# dshield.net
KiCad netlist of a schematic drawn in EAGLE
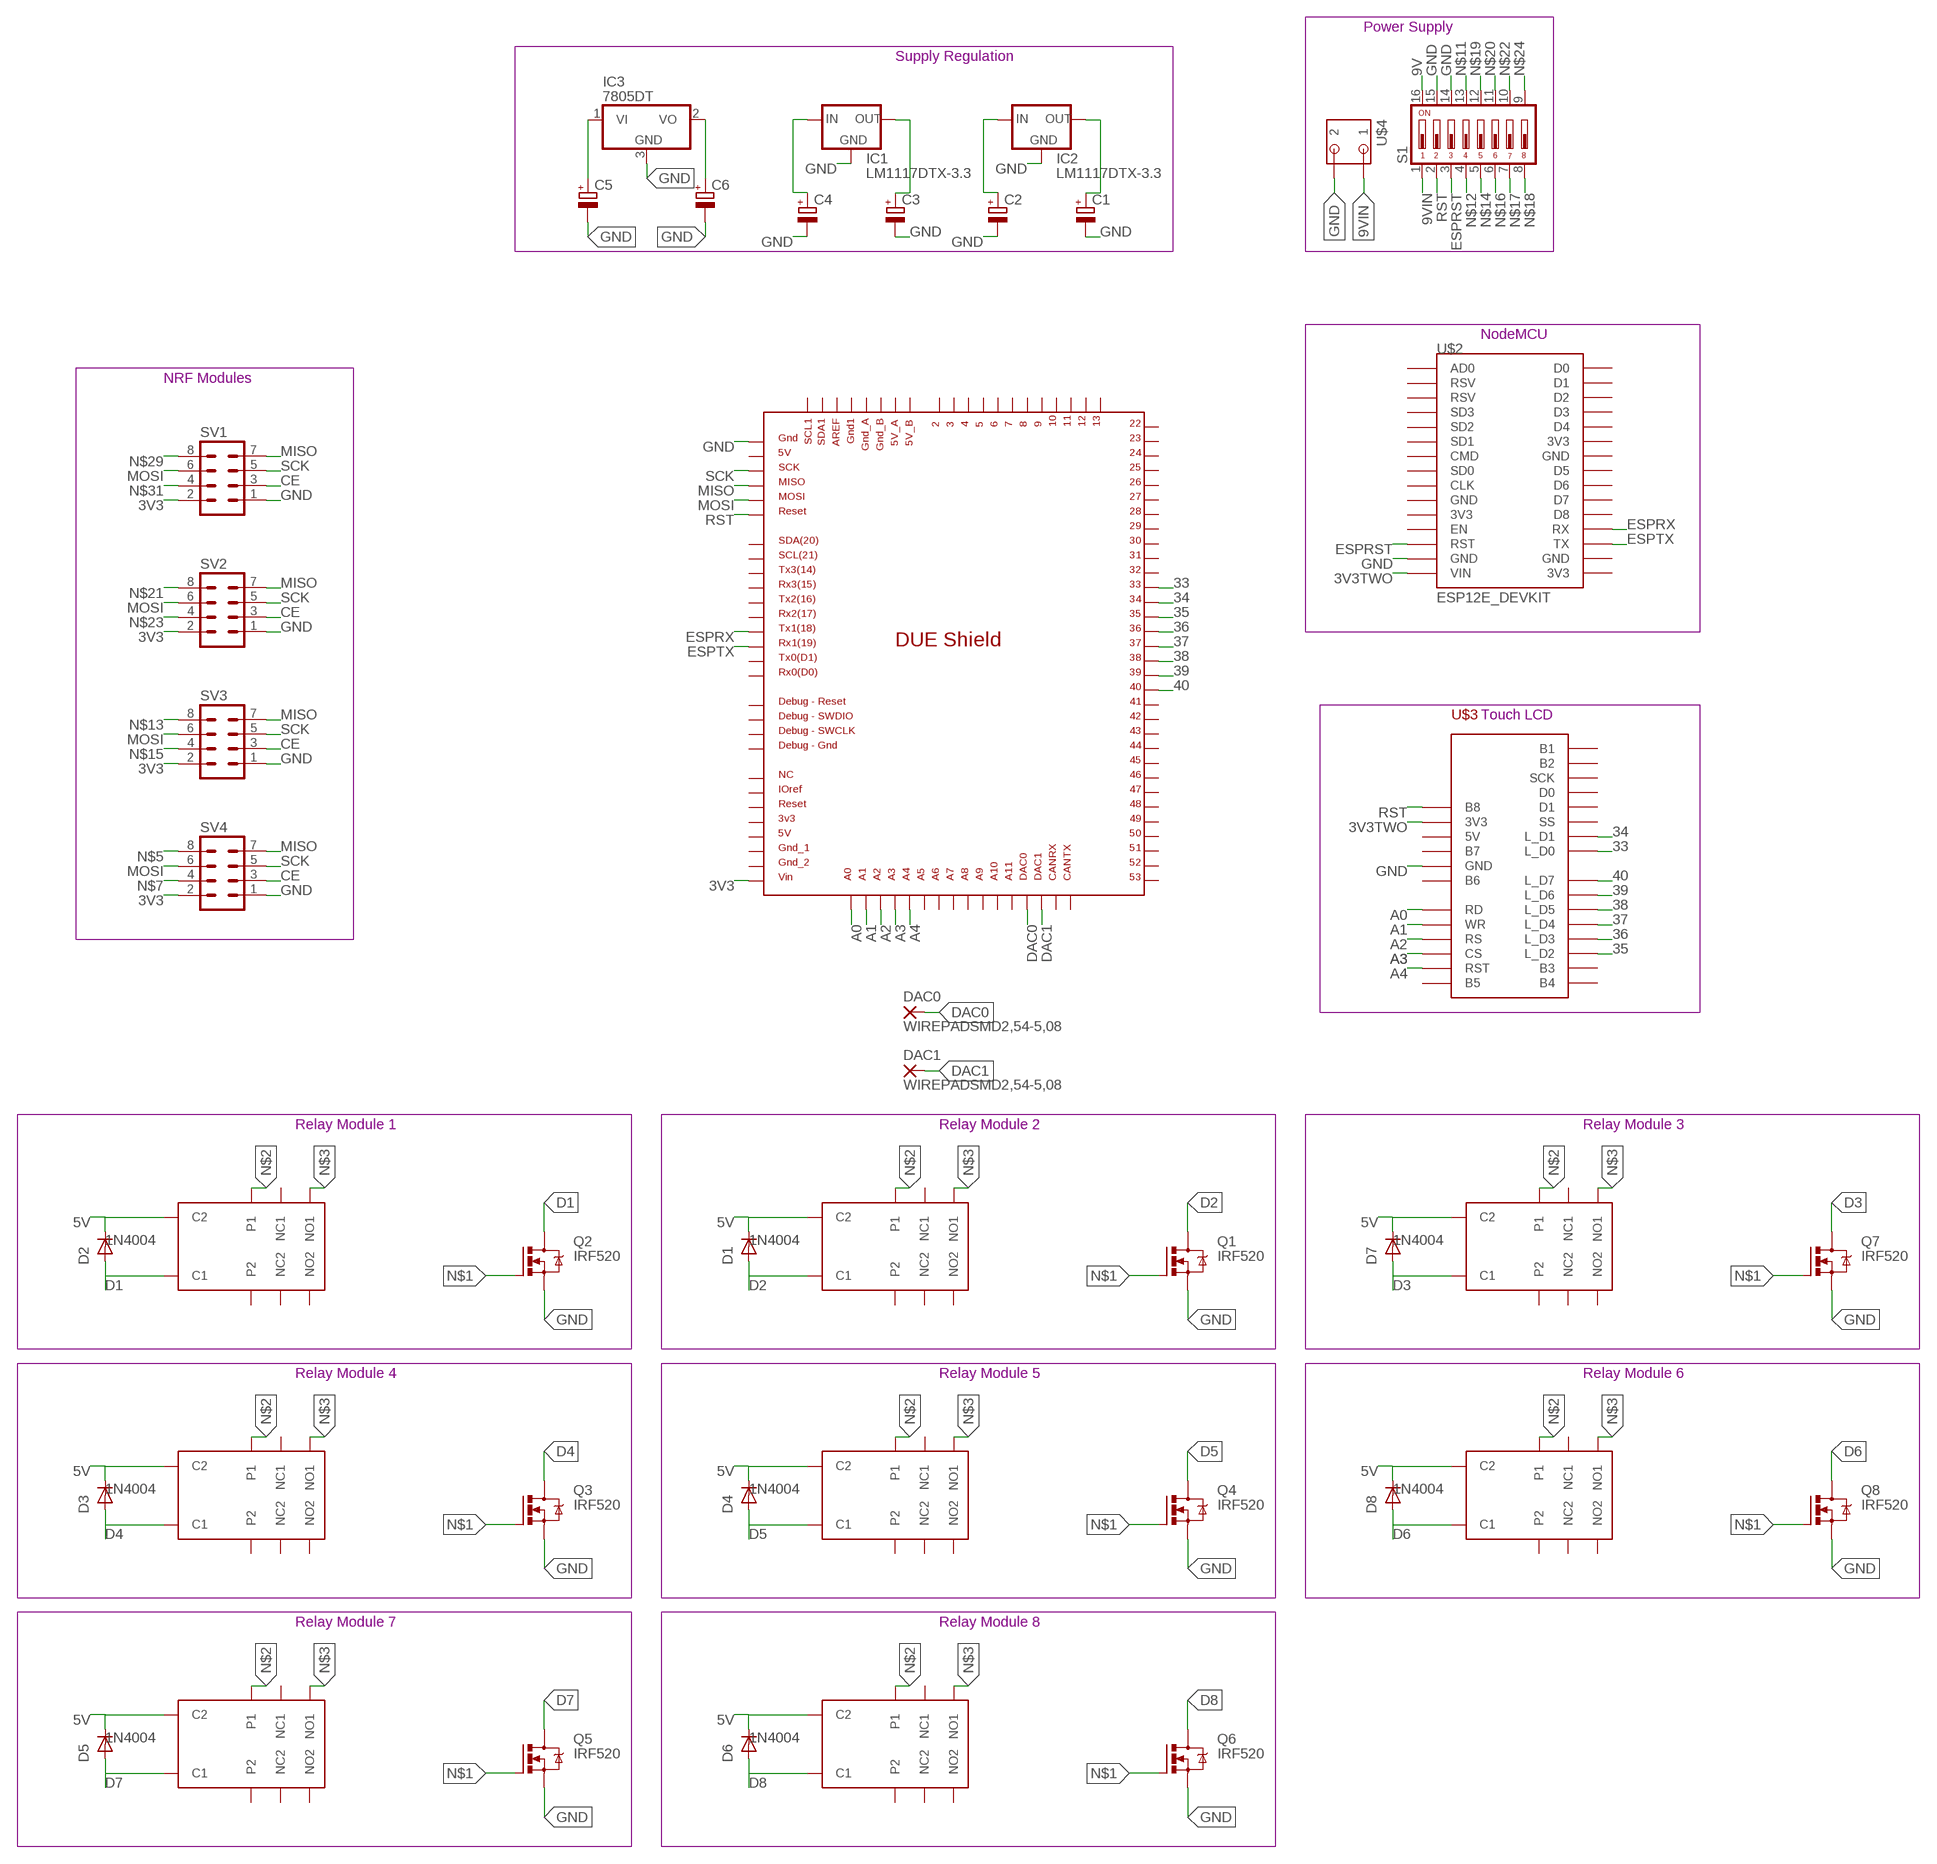
[diagram p0: schematic, sheet 1]

(export (version "E")
  (design (tool "Eeschema 10.0.6"))
  (components
    (comp (ref "BTPL1")
      (value "GS-SH-2XXT")
      (footprint "eagle-import:G_RELAY_SMD")
      (libsource (lib "eagle-import") (part "GS-SH-2XXT"))
    )
    (comp (ref "BTPL2")
      (value "GS-SH-2XXT")
      (footprint "eagle-import:G_RELAY_SMD")
      (libsource (lib "eagle-import") (part "GS-SH-2XXT"))
    )
    (comp (ref "BTPL3")
      (value "GS-SH-2XXT")
      (footprint "eagle-import:G_RELAY_SMD")
      (libsource (lib "eagle-import") (part "GS-SH-2XXT"))
    )
    (comp (ref "BTPL4")
      (value "GS-SH-2XXT")
      (footprint "eagle-import:G_RELAY_SMD")
      (libsource (lib "eagle-import") (part "GS-SH-2XXT"))
    )
    (comp (ref "BTPL5")
      (value "GS-SH-2XXT")
      (footprint "eagle-import:G_RELAY_SMD")
      (libsource (lib "eagle-import") (part "GS-SH-2XXT"))
    )
    (comp (ref "BTPL6")
      (value "GS-SH-2XXT")
      (footprint "eagle-import:G_RELAY_SMD")
      (libsource (lib "eagle-import") (part "GS-SH-2XXT"))
    )
    (comp (ref "BTPL7")
      (value "GS-SH-2XXT")
      (footprint "eagle-import:G_RELAY_SMD")
      (libsource (lib "eagle-import") (part "GS-SH-2XXT"))
    )
    (comp (ref "BTPL8")
      (value "GS-SH-2XXT")
      (footprint "eagle-import:G_RELAY_SMD")
      (libsource (lib "eagle-import") (part "GS-SH-2XXT"))
    )
    (comp (ref "C1")
      (value "CPOL-EUE2.5-6")
      (footprint "eagle-import:E2,5-6")
      (libsource (lib "eagle-import") (part "CPOL-EUE2.5-6"))
    )
    (comp (ref "C2")
      (value "CPOL-EUE2.5-6")
      (footprint "eagle-import:E2,5-6")
      (libsource (lib "eagle-import") (part "CPOL-EUE2.5-6"))
    )
    (comp (ref "C3")
      (value "CPOL-EUE2.5-6")
      (footprint "eagle-import:E2,5-6")
      (libsource (lib "eagle-import") (part "CPOL-EUE2.5-6"))
    )
    (comp (ref "C4")
      (value "CPOL-EUE2.5-6")
      (footprint "eagle-import:E2,5-6")
      (libsource (lib "eagle-import") (part "CPOL-EUE2.5-6"))
    )
    (comp (ref "C5")
      (value "CPOL-EUE2.5-6")
      (footprint "eagle-import:E2,5-6")
      (libsource (lib "eagle-import") (part "CPOL-EUE2.5-6"))
    )
    (comp (ref "C6")
      (value "CPOL-EUE2.5-6")
      (footprint "eagle-import:E2,5-6")
      (libsource (lib "eagle-import") (part "CPOL-EUE2.5-6"))
    )
    (comp (ref "D1")
      (value "1N4004")
      (footprint "eagle-import:DO41-10")
      (libsource (lib "eagle-import") (part "1N4004"))
    )
    (comp (ref "D2")
      (value "1N4004")
      (footprint "eagle-import:DO41-10")
      (libsource (lib "eagle-import") (part "1N4004"))
    )
    (comp (ref "D3")
      (value "1N4004")
      (footprint "eagle-import:DO41-10")
      (libsource (lib "eagle-import") (part "1N4004"))
    )
    (comp (ref "D4")
      (value "1N4004")
      (footprint "eagle-import:DO41-10")
      (libsource (lib "eagle-import") (part "1N4004"))
    )
    (comp (ref "D5")
      (value "1N4004")
      (footprint "eagle-import:DO41-10")
      (libsource (lib "eagle-import") (part "1N4004"))
    )
    (comp (ref "D6")
      (value "1N4004")
      (footprint "eagle-import:DO41-10")
      (libsource (lib "eagle-import") (part "1N4004"))
    )
    (comp (ref "D7")
      (value "1N4004")
      (footprint "eagle-import:DO41-10")
      (libsource (lib "eagle-import") (part "1N4004"))
    )
    (comp (ref "D8")
      (value "1N4004")
      (footprint "eagle-import:DO41-10")
      (libsource (lib "eagle-import") (part "1N4004"))
    )
    (comp (ref "DAC0")
      (value "WIREPADSMD2,54-5,08")
      (footprint "eagle-import:SMD2,54-5,08")
      (libsource (lib "eagle-import") (part "WIREPADSMD2,54-5,08"))
    )
    (comp (ref "DAC1")
      (value "WIREPADSMD2,54-5,08")
      (footprint "eagle-import:SMD2,54-5,08")
      (libsource (lib "eagle-import") (part "WIREPADSMD2,54-5,08"))
    )
    (comp (ref "IC1")
      (value "LM1117DTX-3.3")
      (footprint "eagle-import:TO252")
      (libsource (lib "eagle-import") (part "LM1117DTX-3.3"))
    )
    (comp (ref "IC2")
      (value "LM1117DTX-3.3")
      (footprint "eagle-import:TO252")
      (libsource (lib "eagle-import") (part "LM1117DTX-3.3"))
    )
    (comp (ref "IC3")
      (value "7805DT")
      (footprint "eagle-import:TO252")
      (libsource (lib "eagle-import") (part "78DT05"))
    )
    (comp (ref "Q1")
      (value "IRF520")
      (footprint "eagle-import:TO220BV")
      (libsource (lib "eagle-import") (part "IRF520"))
    )
    (comp (ref "Q2")
      (value "IRF520")
      (footprint "eagle-import:TO220BV")
      (libsource (lib "eagle-import") (part "IRF520"))
    )
    (comp (ref "Q3")
      (value "IRF520")
      (footprint "eagle-import:TO220BV")
      (libsource (lib "eagle-import") (part "IRF520"))
    )
    (comp (ref "Q4")
      (value "IRF520")
      (footprint "eagle-import:TO220BV")
      (libsource (lib "eagle-import") (part "IRF520"))
    )
    (comp (ref "Q5")
      (value "IRF520")
      (footprint "eagle-import:TO220BV")
      (libsource (lib "eagle-import") (part "IRF520"))
    )
    (comp (ref "Q6")
      (value "IRF520")
      (footprint "eagle-import:TO220BV")
      (libsource (lib "eagle-import") (part "IRF520"))
    )
    (comp (ref "Q7")
      (value "IRF520")
      (footprint "eagle-import:TO220BV")
      (libsource (lib "eagle-import") (part "IRF520"))
    )
    (comp (ref "Q8")
      (value "IRF520")
      (footprint "eagle-import:TO220BV")
      (libsource (lib "eagle-import") (part "IRF520"))
    )
    (comp (ref "S1")
      (value "DS08")
      (footprint "eagle-import:DS-08")
      (libsource (lib "eagle-import") (part "DS08"))
    )
    (comp (ref "SV1")
      (value "MA04-2")
      (footprint "eagle-import:MA04-2")
      (libsource (lib "eagle-import") (part "MA04-2"))
    )
    (comp (ref "SV2")
      (value "MA04-2")
      (footprint "eagle-import:MA04-2")
      (libsource (lib "eagle-import") (part "MA04-2"))
    )
    (comp (ref "SV3")
      (value "MA04-2")
      (footprint "eagle-import:MA04-2")
      (libsource (lib "eagle-import") (part "MA04-2"))
    )
    (comp (ref "SV4")
      (value "MA04-2")
      (footprint "eagle-import:MA04-2")
      (libsource (lib "eagle-import") (part "MA04-2"))
    )
    (comp (ref "U$1")
      (value "DUE(NORMAL)")
      (footprint "eagle-import:DUE(NORMAL)")
      (libsource (lib "eagle-import") (part "DUE(NORMAL)"))
    )
    (comp (ref "U$2")
      (value "ESP12E_DEVKIT")
      (footprint "eagle-import:ESP12E_DEVKIT")
      (libsource (lib "eagle-import") (part "ESP12E_DEVKIT"))
    )
    (comp (ref "U$3")
      (value "SPFD5408")
      (footprint "eagle-import:SPFD5408")
      (libsource (lib "eagle-import") (part "SPFD5408"))
    )
    (comp (ref "U$4")
      (value "SPTBB2-A2")
      (footprint "eagle-import:SPTB")
      (libsource (lib "eagle-import") (part "SPTBB2-A2"))
    )
  )
  (nets
    (net (code "1") (name "/3V3") (class "Default")
      (node (ref "C3") (pin "+") (pinfunction "+_+") (pintype "passive"))
      (node (ref "IC1") (pin "TAB") (pinfunction "OUT_TAB") (pintype "passive"))
      (node (ref "SV1") (pin "2") (pinfunction "2_2") (pintype "passive"))
      (node (ref "SV2") (pin "2") (pinfunction "2_2") (pintype "passive"))
      (node (ref "SV3") (pin "2") (pinfunction "2_2") (pintype "passive"))
      (node (ref "SV4") (pin "2") (pinfunction "2_2") (pintype "passive"))
      (node (ref "U$1") (pin "VIN") (pinfunction "VIN_VIN") (pintype "bidirectional"))
    )
    (net (code "2") (name "/3V3TWO") (class "Default")
      (node (ref "C1") (pin "+") (pinfunction "+_+") (pintype "passive"))
      (node (ref "IC2") (pin "TAB") (pinfunction "OUT_TAB") (pintype "passive"))
      (node (ref "U$2") (pin "VIN") (pinfunction "VIN_VIN") (pintype "bidirectional"))
      (node (ref "U$3") (pin "3V3") (pinfunction "3V3_3V3") (pintype "bidirectional"))
    )
    (net (code "3") (name "/5V") (class "Default")
      (node (ref "BTPL1") (pin "C2") (pinfunction "C2_C2") (pintype "bidirectional"))
      (node (ref "BTPL2") (pin "C2") (pinfunction "C2_C2") (pintype "bidirectional"))
      (node (ref "BTPL3") (pin "C2") (pinfunction "C2_C2") (pintype "bidirectional"))
      (node (ref "BTPL4") (pin "C2") (pinfunction "C2_C2") (pintype "bidirectional"))
      (node (ref "BTPL5") (pin "C2") (pinfunction "C2_C2") (pintype "bidirectional"))
      (node (ref "BTPL6") (pin "C2") (pinfunction "C2_C2") (pintype "bidirectional"))
      (node (ref "BTPL7") (pin "C2") (pinfunction "C2_C2") (pintype "bidirectional"))
      (node (ref "BTPL8") (pin "C2") (pinfunction "C2_C2") (pintype "bidirectional"))
      (node (ref "C6") (pin "+") (pinfunction "+_+") (pintype "passive"))
      (node (ref "D1") (pin "C") (pinfunction "C_C") (pintype "passive"))
      (node (ref "D2") (pin "C") (pinfunction "C_C") (pintype "passive"))
      (node (ref "D3") (pin "C") (pinfunction "C_C") (pintype "passive"))
      (node (ref "D4") (pin "C") (pinfunction "C_C") (pintype "passive"))
      (node (ref "D5") (pin "C") (pinfunction "C_C") (pintype "passive"))
      (node (ref "D6") (pin "C") (pinfunction "C_C") (pintype "passive"))
      (node (ref "D7") (pin "C") (pinfunction "C_C") (pintype "passive"))
      (node (ref "D8") (pin "C") (pinfunction "C_C") (pintype "passive"))
      (node (ref "IC3") (pin "2") (pinfunction "VO_2") (pintype "passive"))
    )
    (net (code "4") (name "/9V") (class "Default")
      (node (ref "C2") (pin "+") (pinfunction "+_+") (pintype "passive"))
      (node (ref "C4") (pin "+") (pinfunction "+_+") (pintype "passive"))
      (node (ref "C5") (pin "+") (pinfunction "+_+") (pintype "passive"))
      (node (ref "IC1") (pin "2") (pinfunction "IN_2") (pintype "input"))
      (node (ref "IC2") (pin "2") (pinfunction "IN_2") (pintype "input"))
      (node (ref "IC3") (pin "1") (pinfunction "VI_1") (pintype "input"))
      (node (ref "S1") (pin "16") (pinfunction "16_16") (pintype "passive"))
    )
    (net (code "5") (name "/33") (class "Default")
      (node (ref "U$1") (pin "33") (pinfunction "33_33") (pintype "bidirectional"))
      (node (ref "U$3") (pin "L_D0") (pinfunction "L_D0_L_D0") (pintype "bidirectional"))
    )
    (net (code "6") (name "/34") (class "Default")
      (node (ref "U$1") (pin "34") (pinfunction "34_34") (pintype "bidirectional"))
      (node (ref "U$3") (pin "L_D1") (pinfunction "L_D1_L_D1") (pintype "bidirectional"))
    )
    (net (code "7") (name "/35") (class "Default")
      (node (ref "U$1") (pin "35") (pinfunction "35_35") (pintype "bidirectional"))
      (node (ref "U$3") (pin "L_D2") (pinfunction "L_D2_L_D2") (pintype "bidirectional"))
    )
    (net (code "8") (name "/36") (class "Default")
      (node (ref "U$1") (pin "36") (pinfunction "36_36") (pintype "bidirectional"))
      (node (ref "U$3") (pin "L_D3") (pinfunction "L_D3_L_D3") (pintype "bidirectional"))
    )
    (net (code "9") (name "/37") (class "Default")
      (node (ref "U$1") (pin "37") (pinfunction "37_37") (pintype "bidirectional"))
      (node (ref "U$3") (pin "L_D4") (pinfunction "L_D4_L_D4") (pintype "bidirectional"))
    )
    (net (code "10") (name "/38") (class "Default")
      (node (ref "U$1") (pin "38") (pinfunction "38_38") (pintype "bidirectional"))
      (node (ref "U$3") (pin "L_D5") (pinfunction "L_D5_L_D5") (pintype "bidirectional"))
    )
    (net (code "11") (name "/39") (class "Default")
      (node (ref "U$1") (pin "39") (pinfunction "39_39") (pintype "bidirectional"))
      (node (ref "U$3") (pin "L_D6") (pinfunction "L_D6_L_D6") (pintype "bidirectional"))
    )
    (net (code "12") (name "/40") (class "Default")
      (node (ref "U$1") (pin "40") (pinfunction "40_40") (pintype "bidirectional"))
      (node (ref "U$3") (pin "L_D7") (pinfunction "L_D7_L_D7") (pintype "bidirectional"))
    )
    (net (code "13") (name "/A0") (class "Default")
      (node (ref "U$1") (pin "A0") (pinfunction "A0_A0") (pintype "bidirectional"))
      (node (ref "U$3") (pin "RD") (pinfunction "RD_RD") (pintype "bidirectional"))
    )
    (net (code "14") (name "/A1") (class "Default")
      (node (ref "U$1") (pin "A1") (pinfunction "A1_A1") (pintype "bidirectional"))
      (node (ref "U$3") (pin "WR") (pinfunction "WR_WR") (pintype "bidirectional"))
    )
    (net (code "15") (name "/A2") (class "Default")
      (node (ref "U$1") (pin "A2") (pinfunction "A2_A2") (pintype "bidirectional"))
      (node (ref "U$3") (pin "RS") (pinfunction "RS_RS") (pintype "bidirectional"))
    )
    (net (code "16") (name "/A3") (class "Default")
      (node (ref "U$1") (pin "A3") (pinfunction "A3_A3") (pintype "bidirectional"))
      (node (ref "U$3") (pin "CS") (pinfunction "CS_CS") (pintype "bidirectional"))
    )
    (net (code "17") (name "/A4") (class "Default")
      (node (ref "U$1") (pin "A4") (pinfunction "A4_A4") (pintype "bidirectional"))
      (node (ref "U$3") (pin "RST") (pinfunction "RST_RST") (pintype "bidirectional"))
    )
    (net (code "18") (name "/CE") (class "Default")
      (node (ref "SV1") (pin "3") (pinfunction "3_3") (pintype "passive"))
      (node (ref "SV2") (pin "3") (pinfunction "3_3") (pintype "passive"))
      (node (ref "SV3") (pin "3") (pinfunction "3_3") (pintype "passive"))
      (node (ref "SV4") (pin "3") (pinfunction "3_3") (pintype "passive"))
    )
    (net (code "19") (name "/ESPRST") (class "Default")
      (node (ref "S1") (pin "3") (pinfunction "3_3") (pintype "passive"))
      (node (ref "U$2") (pin "RST") (pinfunction "RST_RST") (pintype "bidirectional"))
    )
    (net (code "20") (name "/ESPRX") (class "Default")
      (node (ref "U$1") (pin "TX1") (pinfunction "TX1_TX1") (pintype "bidirectional"))
      (node (ref "U$2") (pin "RX") (pinfunction "RX_RX") (pintype "bidirectional"))
    )
    (net (code "21") (name "/ESPTX") (class "Default")
      (node (ref "U$1") (pin "RX1") (pinfunction "RX1_RX1") (pintype "bidirectional"))
      (node (ref "U$2") (pin "TX") (pinfunction "TX_TX") (pintype "bidirectional"))
    )
    (net (code "22") (name "/MISO") (class "Default")
      (node (ref "SV1") (pin "7") (pinfunction "7_7") (pintype "passive"))
      (node (ref "SV2") (pin "7") (pinfunction "7_7") (pintype "passive"))
      (node (ref "SV3") (pin "7") (pinfunction "7_7") (pintype "passive"))
      (node (ref "SV4") (pin "7") (pinfunction "7_7") (pintype "passive"))
      (node (ref "U$1") (pin "MISO_ICSP") (pinfunction "MISO_ICSP_MISO_ICSP") (pintype "bidirectional"))
    )
    (net (code "23") (name "/MOSI") (class "Default")
      (node (ref "SV1") (pin "6") (pinfunction "6_6") (pintype "passive"))
      (node (ref "SV2") (pin "6") (pinfunction "6_6") (pintype "passive"))
      (node (ref "SV3") (pin "6") (pinfunction "6_6") (pintype "passive"))
      (node (ref "SV4") (pin "6") (pinfunction "6_6") (pintype "passive"))
      (node (ref "U$1") (pin "MOSI_ICSP") (pinfunction "MOSI_ICSP_MOSI_ICSP") (pintype "bidirectional"))
    )
    (net (code "24") (name "/N$5") (class "Default")
      (node (ref "SV4") (pin "8") (pinfunction "8_8") (pintype "passive"))
    )
    (net (code "25") (name "/N$7") (class "Default")
      (node (ref "SV4") (pin "4") (pinfunction "4_4") (pintype "passive"))
    )
    (net (code "26") (name "/N$11") (class "Default")
      (node (ref "S1") (pin "13") (pinfunction "13_13") (pintype "passive"))
    )
    (net (code "27") (name "/N$12") (class "Default")
      (node (ref "S1") (pin "4") (pinfunction "4_4") (pintype "passive"))
    )
    (net (code "28") (name "/N$13") (class "Default")
      (node (ref "SV3") (pin "8") (pinfunction "8_8") (pintype "passive"))
    )
    (net (code "29") (name "/N$14") (class "Default")
      (node (ref "S1") (pin "5") (pinfunction "5_5") (pintype "passive"))
    )
    (net (code "30") (name "/N$15") (class "Default")
      (node (ref "SV3") (pin "4") (pinfunction "4_4") (pintype "passive"))
    )
    (net (code "31") (name "/N$16") (class "Default")
      (node (ref "S1") (pin "6") (pinfunction "6_6") (pintype "passive"))
    )
    (net (code "32") (name "/N$17") (class "Default")
      (node (ref "S1") (pin "7") (pinfunction "7_7") (pintype "passive"))
    )
    (net (code "33") (name "/N$18") (class "Default")
      (node (ref "S1") (pin "8") (pinfunction "8_8") (pintype "passive"))
    )
    (net (code "34") (name "/N$19") (class "Default")
      (node (ref "S1") (pin "12") (pinfunction "12_12") (pintype "passive"))
    )
    (net (code "35") (name "/N$20") (class "Default")
      (node (ref "S1") (pin "11") (pinfunction "11_11") (pintype "passive"))
    )
    (net (code "36") (name "/N$21") (class "Default")
      (node (ref "SV2") (pin "8") (pinfunction "8_8") (pintype "passive"))
    )
    (net (code "37") (name "/N$22") (class "Default")
      (node (ref "S1") (pin "10") (pinfunction "10_10") (pintype "passive"))
    )
    (net (code "38") (name "/N$23") (class "Default")
      (node (ref "SV2") (pin "4") (pinfunction "4_4") (pintype "passive"))
    )
    (net (code "39") (name "/N$24") (class "Default")
      (node (ref "S1") (pin "9") (pinfunction "9_9") (pintype "passive"))
    )
    (net (code "40") (name "/N$29") (class "Default")
      (node (ref "SV1") (pin "8") (pinfunction "8_8") (pintype "passive"))
    )
    (net (code "41") (name "/N$31") (class "Default")
      (node (ref "SV1") (pin "4") (pinfunction "4_4") (pintype "passive"))
    )
    (net (code "42") (name "/RST") (class "Default")
      (node (ref "S1") (pin "2") (pinfunction "2_2") (pintype "passive"))
      (node (ref "U$1") (pin "RESET_ICSP") (pinfunction "RESET_ICSP_RESET_ICSP") (pintype "bidirectional"))
      (node (ref "U$3") (pin "B8") (pinfunction "B8_B8") (pintype "bidirectional"))
    )
    (net (code "43") (name "/SCK") (class "Default")
      (node (ref "SV1") (pin "5") (pinfunction "5_5") (pintype "passive"))
      (node (ref "SV2") (pin "5") (pinfunction "5_5") (pintype "passive"))
      (node (ref "SV3") (pin "5") (pinfunction "5_5") (pintype "passive"))
      (node (ref "SV4") (pin "5") (pinfunction "5_5") (pintype "passive"))
      (node (ref "U$1") (pin "SCK_ICSP") (pinfunction "SCK_ICSP_SCK_ICSP") (pintype "bidirectional"))
    )
    (net (code "44") (name "9VIN") (class "Default")
      (node (ref "S1") (pin "1") (pinfunction "1_1") (pintype "passive"))
      (node (ref "U$4") (pin "B2") (pinfunction "1_B2") (pintype "bidirectional"))
    )
    (net (code "45") (name "D1") (class "Default")
      (node (ref "BTPL2") (pin "C1") (pinfunction "C1_C1") (pintype "bidirectional"))
      (node (ref "D2") (pin "A") (pinfunction "A_A") (pintype "passive"))
      (node (ref "Q2") (pin "D") (pinfunction "D_D") (pintype "passive"))
    )
    (net (code "46") (name "D2") (class "Default")
      (node (ref "BTPL1") (pin "C1") (pinfunction "C1_C1") (pintype "bidirectional"))
      (node (ref "D1") (pin "A") (pinfunction "A_A") (pintype "passive"))
      (node (ref "Q1") (pin "D") (pinfunction "D_D") (pintype "passive"))
    )
    (net (code "47") (name "D3") (class "Default")
      (node (ref "BTPL7") (pin "C1") (pinfunction "C1_C1") (pintype "bidirectional"))
      (node (ref "D7") (pin "A") (pinfunction "A_A") (pintype "passive"))
      (node (ref "Q7") (pin "D") (pinfunction "D_D") (pintype "passive"))
    )
    (net (code "48") (name "D4") (class "Default")
      (node (ref "BTPL3") (pin "C1") (pinfunction "C1_C1") (pintype "bidirectional"))
      (node (ref "D3") (pin "A") (pinfunction "A_A") (pintype "passive"))
      (node (ref "Q3") (pin "D") (pinfunction "D_D") (pintype "passive"))
    )
    (net (code "49") (name "D5") (class "Default")
      (node (ref "BTPL4") (pin "C1") (pinfunction "C1_C1") (pintype "bidirectional"))
      (node (ref "D4") (pin "A") (pinfunction "A_A") (pintype "passive"))
      (node (ref "Q4") (pin "D") (pinfunction "D_D") (pintype "passive"))
    )
    (net (code "50") (name "D6") (class "Default")
      (node (ref "BTPL8") (pin "C1") (pinfunction "C1_C1") (pintype "bidirectional"))
      (node (ref "D8") (pin "A") (pinfunction "A_A") (pintype "passive"))
      (node (ref "Q8") (pin "D") (pinfunction "D_D") (pintype "passive"))
    )
    (net (code "51") (name "D7") (class "Default")
      (node (ref "BTPL5") (pin "C1") (pinfunction "C1_C1") (pintype "bidirectional"))
      (node (ref "D5") (pin "A") (pinfunction "A_A") (pintype "passive"))
      (node (ref "Q5") (pin "D") (pinfunction "D_D") (pintype "passive"))
    )
    (net (code "52") (name "D8") (class "Default")
      (node (ref "BTPL6") (pin "C1") (pinfunction "C1_C1") (pintype "bidirectional"))
      (node (ref "D6") (pin "A") (pinfunction "A_A") (pintype "passive"))
      (node (ref "Q6") (pin "D") (pinfunction "D_D") (pintype "passive"))
    )
    (net (code "53") (name "DAC0") (class "Default")
      (node (ref "DAC0") (pin "1") (pinfunction "P_1") (pintype "passive"))
      (node (ref "U$1") (pin "DAC0") (pinfunction "DAC0_DAC0") (pintype "bidirectional"))
    )
    (net (code "54") (name "DAC1") (class "Default")
      (node (ref "DAC1") (pin "1") (pinfunction "P_1") (pintype "passive"))
      (node (ref "U$1") (pin "DAC1") (pinfunction "DAC1_DAC1") (pintype "bidirectional"))
    )
    (net (code "55") (name "GND") (class "Default")
      (node (ref "C1") (pin "-") (pinfunction "-_-") (pintype "passive"))
      (node (ref "C2") (pin "-") (pinfunction "-_-") (pintype "passive"))
      (node (ref "C3") (pin "-") (pinfunction "-_-") (pintype "passive"))
      (node (ref "C4") (pin "-") (pinfunction "-_-") (pintype "passive"))
      (node (ref "C5") (pin "-") (pinfunction "-_-") (pintype "passive"))
      (node (ref "C6") (pin "-") (pinfunction "-_-") (pintype "passive"))
      (node (ref "IC1") (pin "1") (pinfunction "GND_1") (pintype "input"))
      (node (ref "IC2") (pin "1") (pinfunction "GND_1") (pintype "input"))
      (node (ref "IC3") (pin "3") (pinfunction "GND_3") (pintype "passive"))
      (node (ref "Q1") (pin "S") (pinfunction "S_S") (pintype "passive"))
      (node (ref "Q2") (pin "S") (pinfunction "S_S") (pintype "passive"))
      (node (ref "Q3") (pin "S") (pinfunction "S_S") (pintype "passive"))
      (node (ref "Q4") (pin "S") (pinfunction "S_S") (pintype "passive"))
      (node (ref "Q5") (pin "S") (pinfunction "S_S") (pintype "passive"))
      (node (ref "Q6") (pin "S") (pinfunction "S_S") (pintype "passive"))
      (node (ref "Q7") (pin "S") (pinfunction "S_S") (pintype "passive"))
      (node (ref "Q8") (pin "S") (pinfunction "S_S") (pintype "passive"))
      (node (ref "S1") (pin "14") (pinfunction "14_14") (pintype "passive"))
      (node (ref "S1") (pin "15") (pinfunction "15_15") (pintype "passive"))
      (node (ref "SV1") (pin "1") (pinfunction "1_1") (pintype "passive"))
      (node (ref "SV2") (pin "1") (pinfunction "1_1") (pintype "passive"))
      (node (ref "SV3") (pin "1") (pinfunction "1_1") (pintype "passive"))
      (node (ref "SV4") (pin "1") (pinfunction "1_1") (pintype "passive"))
      (node (ref "U$1") (pin "5V_ICSP") (pinfunction "5V_ICSP_5V_ICSP") (pintype "bidirectional"))
      (node (ref "U$2") (pin "GND@1") (pinfunction "GND_GND@1") (pintype "bidirectional"))
      (node (ref "U$3") (pin "GND") (pinfunction "GND_GND") (pintype "bidirectional"))
      (node (ref "U$4") (pin "A2") (pinfunction "2_A2") (pintype "bidirectional"))
    )
    (net (code "56") (name "N$1") (class "Default")
      (node (ref "Q1") (pin "G") (pinfunction "G_G") (pintype "passive"))
      (node (ref "Q2") (pin "G") (pinfunction "G_G") (pintype "passive"))
      (node (ref "Q3") (pin "G") (pinfunction "G_G") (pintype "passive"))
      (node (ref "Q4") (pin "G") (pinfunction "G_G") (pintype "passive"))
      (node (ref "Q5") (pin "G") (pinfunction "G_G") (pintype "passive"))
      (node (ref "Q6") (pin "G") (pinfunction "G_G") (pintype "passive"))
      (node (ref "Q7") (pin "G") (pinfunction "G_G") (pintype "passive"))
      (node (ref "Q8") (pin "G") (pinfunction "G_G") (pintype "passive"))
    )
    (net (code "57") (name "N$2") (class "Default")
      (node (ref "BTPL1") (pin "P1") (pinfunction "P1_P1") (pintype "bidirectional"))
      (node (ref "BTPL2") (pin "P1") (pinfunction "P1_P1") (pintype "bidirectional"))
      (node (ref "BTPL3") (pin "P1") (pinfunction "P1_P1") (pintype "bidirectional"))
      (node (ref "BTPL4") (pin "P1") (pinfunction "P1_P1") (pintype "bidirectional"))
      (node (ref "BTPL5") (pin "P1") (pinfunction "P1_P1") (pintype "bidirectional"))
      (node (ref "BTPL6") (pin "P1") (pinfunction "P1_P1") (pintype "bidirectional"))
      (node (ref "BTPL7") (pin "P1") (pinfunction "P1_P1") (pintype "bidirectional"))
      (node (ref "BTPL8") (pin "P1") (pinfunction "P1_P1") (pintype "bidirectional"))
    )
    (net (code "58") (name "N$3") (class "Default")
      (node (ref "BTPL1") (pin "NO1") (pinfunction "NO1_NO1") (pintype "output"))
      (node (ref "BTPL2") (pin "NO1") (pinfunction "NO1_NO1") (pintype "output"))
      (node (ref "BTPL3") (pin "NO1") (pinfunction "NO1_NO1") (pintype "output"))
      (node (ref "BTPL4") (pin "NO1") (pinfunction "NO1_NO1") (pintype "output"))
      (node (ref "BTPL5") (pin "NO1") (pinfunction "NO1_NO1") (pintype "output"))
      (node (ref "BTPL6") (pin "NO1") (pinfunction "NO1_NO1") (pintype "output"))
      (node (ref "BTPL7") (pin "NO1") (pinfunction "NO1_NO1") (pintype "output"))
      (node (ref "BTPL8") (pin "NO1") (pinfunction "NO1_NO1") (pintype "output"))
    )
    (net (code "59") (name "unconnected-(BTPL1-PadNC1)") (class "Default")
      (node (ref "BTPL1") (pin "NC1") (pinfunction "NC1_NC1") (pintype "output"))
    )
    (net (code "60") (name "unconnected-(BTPL1-PadNC2)") (class "Default")
      (node (ref "BTPL1") (pin "NC2") (pinfunction "NC2_NC2") (pintype "output"))
    )
    (net (code "61") (name "unconnected-(BTPL1-PadNO2)") (class "Default")
      (node (ref "BTPL1") (pin "NO2") (pinfunction "NO2_NO2") (pintype "output"))
    )
    (net (code "62") (name "unconnected-(BTPL1-PadP2)") (class "Default")
      (node (ref "BTPL1") (pin "P2") (pinfunction "P2_P2") (pintype "bidirectional"))
    )
    (net (code "63") (name "unconnected-(BTPL2-PadNC1)") (class "Default")
      (node (ref "BTPL2") (pin "NC1") (pinfunction "NC1_NC1") (pintype "output"))
    )
    (net (code "64") (name "unconnected-(BTPL2-PadNC2)") (class "Default")
      (node (ref "BTPL2") (pin "NC2") (pinfunction "NC2_NC2") (pintype "output"))
    )
    (net (code "65") (name "unconnected-(BTPL2-PadNO2)") (class "Default")
      (node (ref "BTPL2") (pin "NO2") (pinfunction "NO2_NO2") (pintype "output"))
    )
    (net (code "66") (name "unconnected-(BTPL2-PadP2)") (class "Default")
      (node (ref "BTPL2") (pin "P2") (pinfunction "P2_P2") (pintype "bidirectional"))
    )
    (net (code "67") (name "unconnected-(BTPL3-PadNC1)") (class "Default")
      (node (ref "BTPL3") (pin "NC1") (pinfunction "NC1_NC1") (pintype "output"))
    )
    (net (code "68") (name "unconnected-(BTPL3-PadNC2)") (class "Default")
      (node (ref "BTPL3") (pin "NC2") (pinfunction "NC2_NC2") (pintype "output"))
    )
    (net (code "69") (name "unconnected-(BTPL3-PadNO2)") (class "Default")
      (node (ref "BTPL3") (pin "NO2") (pinfunction "NO2_NO2") (pintype "output"))
    )
    (net (code "70") (name "unconnected-(BTPL3-PadP2)") (class "Default")
      (node (ref "BTPL3") (pin "P2") (pinfunction "P2_P2") (pintype "bidirectional"))
    )
    (net (code "71") (name "unconnected-(BTPL4-PadNC1)") (class "Default")
      (node (ref "BTPL4") (pin "NC1") (pinfunction "NC1_NC1") (pintype "output"))
    )
    (net (code "72") (name "unconnected-(BTPL4-PadNC2)") (class "Default")
      (node (ref "BTPL4") (pin "NC2") (pinfunction "NC2_NC2") (pintype "output"))
    )
    (net (code "73") (name "unconnected-(BTPL4-PadNO2)") (class "Default")
      (node (ref "BTPL4") (pin "NO2") (pinfunction "NO2_NO2") (pintype "output"))
    )
    (net (code "74") (name "unconnected-(BTPL4-PadP2)") (class "Default")
      (node (ref "BTPL4") (pin "P2") (pinfunction "P2_P2") (pintype "bidirectional"))
    )
    (net (code "75") (name "unconnected-(BTPL5-PadNC1)") (class "Default")
      (node (ref "BTPL5") (pin "NC1") (pinfunction "NC1_NC1") (pintype "output"))
    )
    (net (code "76") (name "unconnected-(BTPL5-PadNC2)") (class "Default")
      (node (ref "BTPL5") (pin "NC2") (pinfunction "NC2_NC2") (pintype "output"))
    )
    (net (code "77") (name "unconnected-(BTPL5-PadNO2)") (class "Default")
      (node (ref "BTPL5") (pin "NO2") (pinfunction "NO2_NO2") (pintype "output"))
    )
    (net (code "78") (name "unconnected-(BTPL5-PadP2)") (class "Default")
      (node (ref "BTPL5") (pin "P2") (pinfunction "P2_P2") (pintype "bidirectional"))
    )
    (net (code "79") (name "unconnected-(BTPL6-PadNC1)") (class "Default")
      (node (ref "BTPL6") (pin "NC1") (pinfunction "NC1_NC1") (pintype "output"))
    )
    (net (code "80") (name "unconnected-(BTPL6-PadNC2)") (class "Default")
      (node (ref "BTPL6") (pin "NC2") (pinfunction "NC2_NC2") (pintype "output"))
    )
    (net (code "81") (name "unconnected-(BTPL6-PadNO2)") (class "Default")
      (node (ref "BTPL6") (pin "NO2") (pinfunction "NO2_NO2") (pintype "output"))
    )
    (net (code "82") (name "unconnected-(BTPL6-PadP2)") (class "Default")
      (node (ref "BTPL6") (pin "P2") (pinfunction "P2_P2") (pintype "bidirectional"))
    )
    (net (code "83") (name "unconnected-(BTPL7-PadNC1)") (class "Default")
      (node (ref "BTPL7") (pin "NC1") (pinfunction "NC1_NC1") (pintype "output"))
    )
    (net (code "84") (name "unconnected-(BTPL7-PadNC2)") (class "Default")
      (node (ref "BTPL7") (pin "NC2") (pinfunction "NC2_NC2") (pintype "output"))
    )
    (net (code "85") (name "unconnected-(BTPL7-PadNO2)") (class "Default")
      (node (ref "BTPL7") (pin "NO2") (pinfunction "NO2_NO2") (pintype "output"))
    )
    (net (code "86") (name "unconnected-(BTPL7-PadP2)") (class "Default")
      (node (ref "BTPL7") (pin "P2") (pinfunction "P2_P2") (pintype "bidirectional"))
    )
    (net (code "87") (name "unconnected-(BTPL8-PadNC1)") (class "Default")
      (node (ref "BTPL8") (pin "NC1") (pinfunction "NC1_NC1") (pintype "output"))
    )
    (net (code "88") (name "unconnected-(BTPL8-PadNC2)") (class "Default")
      (node (ref "BTPL8") (pin "NC2") (pinfunction "NC2_NC2") (pintype "output"))
    )
    (net (code "89") (name "unconnected-(BTPL8-PadNO2)") (class "Default")
      (node (ref "BTPL8") (pin "NO2") (pinfunction "NO2_NO2") (pintype "output"))
    )
    (net (code "90") (name "unconnected-(BTPL8-PadP2)") (class "Default")
      (node (ref "BTPL8") (pin "P2") (pinfunction "P2_P2") (pintype "bidirectional"))
    )
    (net (code "91") (name "unconnected-(U$1-Pad2)") (class "Default")
      (node (ref "U$1") (pin "2") (pinfunction "2_2") (pintype "bidirectional"))
    )
    (net (code "92") (name "unconnected-(U$1-Pad3)") (class "Default")
      (node (ref "U$1") (pin "3") (pinfunction "3_3") (pintype "bidirectional"))
    )
    (net (code "93") (name "unconnected-(U$1-Pad3V3)") (class "Default")
      (node (ref "U$1") (pin "3V3") (pinfunction "3V3_3V3") (pintype "bidirectional"))
    )
    (net (code "94") (name "unconnected-(U$1-Pad4)") (class "Default")
      (node (ref "U$1") (pin "4") (pinfunction "4_4") (pintype "bidirectional"))
    )
    (net (code "95") (name "unconnected-(U$1-Pad5)") (class "Default")
      (node (ref "U$1") (pin "5") (pinfunction "5_5") (pintype "bidirectional"))
    )
    (net (code "96") (name "unconnected-(U$1-Pad5V)") (class "Default")
      (node (ref "U$1") (pin "5V") (pinfunction "5V_5V") (pintype "bidirectional"))
    )
    (net (code "97") (name "unconnected-(U$1-Pad5V_A)") (class "Default")
      (node (ref "U$1") (pin "5V_A") (pinfunction "5V_A_5V_A") (pintype "bidirectional"))
    )
    (net (code "98") (name "unconnected-(U$1-Pad5V_B)") (class "Default")
      (node (ref "U$1") (pin "5V_B") (pinfunction "5V_B_5V_B") (pintype "bidirectional"))
    )
    (net (code "99") (name "unconnected-(U$1-Pad6)") (class "Default")
      (node (ref "U$1") (pin "6") (pinfunction "6_6") (pintype "bidirectional"))
    )
    (net (code "100") (name "unconnected-(U$1-Pad7)") (class "Default")
      (node (ref "U$1") (pin "7") (pinfunction "7_7") (pintype "bidirectional"))
    )
    (net (code "101") (name "unconnected-(U$1-Pad8)") (class "Default")
      (node (ref "U$1") (pin "8") (pinfunction "8_8") (pintype "bidirectional"))
    )
    (net (code "102") (name "unconnected-(U$1-Pad9)") (class "Default")
      (node (ref "U$1") (pin "9") (pinfunction "9_9") (pintype "bidirectional"))
    )
    (net (code "103") (name "unconnected-(U$1-Pad10)") (class "Default")
      (node (ref "U$1") (pin "10") (pinfunction "10_10") (pintype "bidirectional"))
    )
    (net (code "104") (name "unconnected-(U$1-Pad11)") (class "Default")
      (node (ref "U$1") (pin "11") (pinfunction "11_11") (pintype "bidirectional"))
    )
    (net (code "105") (name "unconnected-(U$1-Pad12)") (class "Default")
      (node (ref "U$1") (pin "12") (pinfunction "12_12") (pintype "bidirectional"))
    )
    (net (code "106") (name "unconnected-(U$1-Pad13)") (class "Default")
      (node (ref "U$1") (pin "13") (pinfunction "13_13") (pintype "bidirectional"))
    )
    (net (code "107") (name "unconnected-(U$1-Pad22)") (class "Default")
      (node (ref "U$1") (pin "22") (pinfunction "22_22") (pintype "bidirectional"))
    )
    (net (code "108") (name "unconnected-(U$1-Pad23)") (class "Default")
      (node (ref "U$1") (pin "23") (pinfunction "23_23") (pintype "bidirectional"))
    )
    (net (code "109") (name "unconnected-(U$1-Pad24)") (class "Default")
      (node (ref "U$1") (pin "24") (pinfunction "24_24") (pintype "bidirectional"))
    )
    (net (code "110") (name "unconnected-(U$1-Pad25)") (class "Default")
      (node (ref "U$1") (pin "25") (pinfunction "25_25") (pintype "bidirectional"))
    )
    (net (code "111") (name "unconnected-(U$1-Pad26)") (class "Default")
      (node (ref "U$1") (pin "26") (pinfunction "26_26") (pintype "bidirectional"))
    )
    (net (code "112") (name "unconnected-(U$1-Pad27)") (class "Default")
      (node (ref "U$1") (pin "27") (pinfunction "27_27") (pintype "bidirectional"))
    )
    (net (code "113") (name "unconnected-(U$1-Pad28)") (class "Default")
      (node (ref "U$1") (pin "28") (pinfunction "28_28") (pintype "bidirectional"))
    )
    (net (code "114") (name "unconnected-(U$1-Pad29)") (class "Default")
      (node (ref "U$1") (pin "29") (pinfunction "29_29") (pintype "bidirectional"))
    )
    (net (code "115") (name "unconnected-(U$1-Pad30)") (class "Default")
      (node (ref "U$1") (pin "30") (pinfunction "30_30") (pintype "bidirectional"))
    )
    (net (code "116") (name "unconnected-(U$1-Pad31)") (class "Default")
      (node (ref "U$1") (pin "31") (pinfunction "31_31") (pintype "bidirectional"))
    )
    (net (code "117") (name "unconnected-(U$1-Pad32)") (class "Default")
      (node (ref "U$1") (pin "32") (pinfunction "32_32") (pintype "bidirectional"))
    )
    (net (code "118") (name "unconnected-(U$1-Pad41)") (class "Default")
      (node (ref "U$1") (pin "41") (pinfunction "41_41") (pintype "bidirectional"))
    )
    (net (code "119") (name "unconnected-(U$1-Pad42)") (class "Default")
      (node (ref "U$1") (pin "42") (pinfunction "42_42") (pintype "bidirectional"))
    )
    (net (code "120") (name "unconnected-(U$1-Pad43)") (class "Default")
      (node (ref "U$1") (pin "43") (pinfunction "43_43") (pintype "bidirectional"))
    )
    (net (code "121") (name "unconnected-(U$1-Pad44)") (class "Default")
      (node (ref "U$1") (pin "44") (pinfunction "44_44") (pintype "bidirectional"))
    )
    (net (code "122") (name "unconnected-(U$1-Pad45)") (class "Default")
      (node (ref "U$1") (pin "45") (pinfunction "45_45") (pintype "bidirectional"))
    )
    (net (code "123") (name "unconnected-(U$1-Pad46)") (class "Default")
      (node (ref "U$1") (pin "46") (pinfunction "46_46") (pintype "bidirectional"))
    )
    (net (code "124") (name "unconnected-(U$1-Pad47)") (class "Default")
      (node (ref "U$1") (pin "47") (pinfunction "47_47") (pintype "bidirectional"))
    )
    (net (code "125") (name "unconnected-(U$1-Pad48)") (class "Default")
      (node (ref "U$1") (pin "48") (pinfunction "48_48") (pintype "bidirectional"))
    )
    (net (code "126") (name "unconnected-(U$1-Pad49)") (class "Default")
      (node (ref "U$1") (pin "49") (pinfunction "49_49") (pintype "bidirectional"))
    )
    (net (code "127") (name "unconnected-(U$1-Pad50)") (class "Default")
      (node (ref "U$1") (pin "50") (pinfunction "50_50") (pintype "bidirectional"))
    )
    (net (code "128") (name "unconnected-(U$1-Pad51)") (class "Default")
      (node (ref "U$1") (pin "51") (pinfunction "51_51") (pintype "bidirectional"))
    )
    (net (code "129") (name "unconnected-(U$1-Pad52)") (class "Default")
      (node (ref "U$1") (pin "52") (pinfunction "52_52") (pintype "bidirectional"))
    )
    (net (code "130") (name "unconnected-(U$1-Pad53)") (class "Default")
      (node (ref "U$1") (pin "53") (pinfunction "53_53") (pintype "bidirectional"))
    )
    (net (code "131") (name "unconnected-(U$1-PadA5)") (class "Default")
      (node (ref "U$1") (pin "A5") (pinfunction "A5_A5") (pintype "bidirectional"))
    )
    (net (code "132") (name "unconnected-(U$1-PadA6)") (class "Default")
      (node (ref "U$1") (pin "A6") (pinfunction "A6_A6") (pintype "bidirectional"))
    )
    (net (code "133") (name "unconnected-(U$1-PadA7)") (class "Default")
      (node (ref "U$1") (pin "A7") (pinfunction "A7_A7") (pintype "bidirectional"))
    )
    (net (code "134") (name "unconnected-(U$1-PadA8)") (class "Default")
      (node (ref "U$1") (pin "A8") (pinfunction "A8_A8") (pintype "bidirectional"))
    )
    (net (code "135") (name "unconnected-(U$1-PadA9)") (class "Default")
      (node (ref "U$1") (pin "A9") (pinfunction "A9_A9") (pintype "bidirectional"))
    )
    (net (code "136") (name "unconnected-(U$1-PadA10)") (class "Default")
      (node (ref "U$1") (pin "A10") (pinfunction "A10_A10") (pintype "bidirectional"))
    )
    (net (code "137") (name "unconnected-(U$1-PadA11)") (class "Default")
      (node (ref "U$1") (pin "A11") (pinfunction "A11_A11") (pintype "bidirectional"))
    )
    (net (code "138") (name "unconnected-(U$1-PadAREF)") (class "Default")
      (node (ref "U$1") (pin "AREF") (pinfunction "AREF_AREF") (pintype "bidirectional"))
    )
    (net (code "139") (name "unconnected-(U$1-PadCANRX)") (class "Default")
      (node (ref "U$1") (pin "CANRX") (pinfunction "CANRX_CANRX") (pintype "bidirectional"))
    )
    (net (code "140") (name "unconnected-(U$1-PadCANTX)") (class "Default")
      (node (ref "U$1") (pin "CANTX") (pinfunction "CANTX_CANTX") (pintype "bidirectional"))
    )
    (net (code "141") (name "unconnected-(U$1-PadGND1)") (class "Default")
      (node (ref "U$1") (pin "GND1") (pinfunction "GND1_GND1") (pintype "bidirectional"))
    )
    (net (code "142") (name "unconnected-(U$1-PadGND_1)") (class "Default")
      (node (ref "U$1") (pin "GND_1") (pinfunction "GND_1_GND_1") (pintype "bidirectional"))
    )
    (net (code "143") (name "unconnected-(U$1-PadGND_2)") (class "Default")
      (node (ref "U$1") (pin "GND_2") (pinfunction "GND_2_GND_2") (pintype "bidirectional"))
    )
    (net (code "144") (name "unconnected-(U$1-PadGND_A)") (class "Default")
      (node (ref "U$1") (pin "GND_A") (pinfunction "GND_A_GND_A") (pintype "bidirectional"))
    )
    (net (code "145") (name "unconnected-(U$1-PadGND_B)") (class "Default")
      (node (ref "U$1") (pin "GND_B") (pinfunction "GND_B_GND_B") (pintype "bidirectional"))
    )
    (net (code "146") (name "unconnected-(U$1-PadGND_DEBUG)") (class "Default")
      (node (ref "U$1") (pin "GND_DEBUG") (pinfunction "GND_DEBUG_GND_DEBUG") (pintype "bidirectional"))
    )
    (net (code "147") (name "unconnected-(U$1-PadGND_ICSP)") (class "Default")
      (node (ref "U$1") (pin "GND_ICSP") (pinfunction "GND_ICSP_GND_ICSP") (pintype "bidirectional"))
    )
    (net (code "148") (name "unconnected-(U$1-PadIOREF)") (class "Default")
      (node (ref "U$1") (pin "IOREF") (pinfunction "IOREF_IOREF") (pintype "bidirectional"))
    )
    (net (code "149") (name "unconnected-(U$1-PadNC)") (class "Default")
      (node (ref "U$1") (pin "NC") (pinfunction "NC_NC") (pintype "bidirectional"))
    )
    (net (code "150") (name "unconnected-(U$1-PadRESET)") (class "Default")
      (node (ref "U$1") (pin "RESET") (pinfunction "RESET_RESET") (pintype "bidirectional"))
    )
    (net (code "151") (name "unconnected-(U$1-PadRESET_DEBUG)") (class "Default")
      (node (ref "U$1") (pin "RESET_DEBUG") (pinfunction "RESET_DEBUG_RESET_DEBUG") (pintype "bidirectional"))
    )
    (net (code "152") (name "unconnected-(U$1-PadRX0)") (class "Default")
      (node (ref "U$1") (pin "RX0") (pinfunction "RX0_RX0") (pintype "bidirectional"))
    )
    (net (code "153") (name "unconnected-(U$1-PadRX2)") (class "Default")
      (node (ref "U$1") (pin "RX2") (pinfunction "RX2_RX2") (pintype "bidirectional"))
    )
    (net (code "154") (name "unconnected-(U$1-PadRX3)") (class "Default")
      (node (ref "U$1") (pin "RX3") (pinfunction "RX3_RX3") (pintype "bidirectional"))
    )
    (net (code "155") (name "unconnected-(U$1-PadSCL)") (class "Default")
      (node (ref "U$1") (pin "SCL") (pinfunction "SCL_SCL") (pintype "bidirectional"))
    )
    (net (code "156") (name "unconnected-(U$1-PadSCL1)") (class "Default")
      (node (ref "U$1") (pin "SCL1") (pinfunction "SCL1_SCL1") (pintype "bidirectional"))
    )
    (net (code "157") (name "unconnected-(U$1-PadSDA)") (class "Default")
      (node (ref "U$1") (pin "SDA") (pinfunction "SDA_SDA") (pintype "bidirectional"))
    )
    (net (code "158") (name "unconnected-(U$1-PadSDA1)") (class "Default")
      (node (ref "U$1") (pin "SDA1") (pinfunction "SDA1_SDA1") (pintype "bidirectional"))
    )
    (net (code "159") (name "unconnected-(U$1-PadSWCLK_DEBUG)") (class "Default")
      (node (ref "U$1") (pin "SWCLK_DEBUG") (pinfunction "SWCLK_DEBUG_SWCLK_DEBUG") (pintype "bidirectional"))
    )
    (net (code "160") (name "unconnected-(U$1-PadSWDIO_DEBUG)") (class "Default")
      (node (ref "U$1") (pin "SWDIO_DEBUG") (pinfunction "SWDIO_DEBUG_SWDIO_DEBUG") (pintype "bidirectional"))
    )
    (net (code "161") (name "unconnected-(U$1-PadTX0)") (class "Default")
      (node (ref "U$1") (pin "TX0") (pinfunction "TX0_TX0") (pintype "bidirectional"))
    )
    (net (code "162") (name "unconnected-(U$1-PadTX2)") (class "Default")
      (node (ref "U$1") (pin "TX2") (pinfunction "TX2_TX2") (pintype "bidirectional"))
    )
    (net (code "163") (name "unconnected-(U$1-PadTX3)") (class "Default")
      (node (ref "U$1") (pin "TX3") (pinfunction "TX3_TX3") (pintype "bidirectional"))
    )
    (net (code "164") (name "unconnected-(U$2-3V3-Pad3V3@0)") (class "Default")
      (node (ref "U$2") (pin "3V3@0") (pinfunction "3V3_3V3@0") (pintype "bidirectional"))
    )
    (net (code "165") (name "unconnected-(U$2-3V3-Pad3V3@1)") (class "Default")
      (node (ref "U$2") (pin "3V3@1") (pinfunction "3V3_3V3@1") (pintype "bidirectional"))
    )
    (net (code "166") (name "unconnected-(U$2-3V3-Pad3V3@2)") (class "Default")
      (node (ref "U$2") (pin "3V3@2") (pinfunction "3V3_3V3@2") (pintype "bidirectional"))
    )
    (net (code "167") (name "unconnected-(U$2-GND-PadGND@0)") (class "Default")
      (node (ref "U$2") (pin "GND@0") (pinfunction "GND_GND@0") (pintype "bidirectional"))
    )
    (net (code "168") (name "unconnected-(U$2-GND-PadGND@2)") (class "Default")
      (node (ref "U$2") (pin "GND@2") (pinfunction "GND_GND@2") (pintype "bidirectional"))
    )
    (net (code "169") (name "unconnected-(U$2-GND-PadGND@3)") (class "Default")
      (node (ref "U$2") (pin "GND@3") (pinfunction "GND_GND@3") (pintype "bidirectional"))
    )
    (net (code "170") (name "unconnected-(U$2-PadAD0)") (class "Default")
      (node (ref "U$2") (pin "AD0") (pinfunction "AD0_AD0") (pintype "bidirectional"))
    )
    (net (code "171") (name "unconnected-(U$2-PadCLK)") (class "Default")
      (node (ref "U$2") (pin "CLK") (pinfunction "CLK_CLK") (pintype "bidirectional"))
    )
    (net (code "172") (name "unconnected-(U$2-PadCMD)") (class "Default")
      (node (ref "U$2") (pin "CMD") (pinfunction "CMD_CMD") (pintype "bidirectional"))
    )
    (net (code "173") (name "unconnected-(U$2-PadD0)") (class "Default")
      (node (ref "U$2") (pin "D0") (pinfunction "D0_D0") (pintype "bidirectional"))
    )
    (net (code "174") (name "unconnected-(U$2-PadD1)") (class "Default")
      (node (ref "U$2") (pin "D1") (pinfunction "D1_D1") (pintype "bidirectional"))
    )
    (net (code "175") (name "unconnected-(U$2-PadD2)") (class "Default")
      (node (ref "U$2") (pin "D2") (pinfunction "D2_D2") (pintype "bidirectional"))
    )
    (net (code "176") (name "unconnected-(U$2-PadD3)") (class "Default")
      (node (ref "U$2") (pin "D3") (pinfunction "D3_D3") (pintype "bidirectional"))
    )
    (net (code "177") (name "unconnected-(U$2-PadD4)") (class "Default")
      (node (ref "U$2") (pin "D4") (pinfunction "D4_D4") (pintype "bidirectional"))
    )
    (net (code "178") (name "unconnected-(U$2-PadD5)") (class "Default")
      (node (ref "U$2") (pin "D5") (pinfunction "D5_D5") (pintype "bidirectional"))
    )
    (net (code "179") (name "unconnected-(U$2-PadD6)") (class "Default")
      (node (ref "U$2") (pin "D6") (pinfunction "D6_D6") (pintype "bidirectional"))
    )
    (net (code "180") (name "unconnected-(U$2-PadD7)") (class "Default")
      (node (ref "U$2") (pin "D7") (pinfunction "D7_D7") (pintype "bidirectional"))
    )
    (net (code "181") (name "unconnected-(U$2-PadD8)") (class "Default")
      (node (ref "U$2") (pin "D8") (pinfunction "D8_D8") (pintype "bidirectional"))
    )
    (net (code "182") (name "unconnected-(U$2-PadEN)") (class "Default")
      (node (ref "U$2") (pin "EN") (pinfunction "EN_EN") (pintype "bidirectional"))
    )
    (net (code "183") (name "unconnected-(U$2-PadSD0)") (class "Default")
      (node (ref "U$2") (pin "SD0") (pinfunction "SD0_SD0") (pintype "bidirectional"))
    )
    (net (code "184") (name "unconnected-(U$2-PadSD1)") (class "Default")
      (node (ref "U$2") (pin "SD1") (pinfunction "SD1_SD1") (pintype "bidirectional"))
    )
    (net (code "185") (name "unconnected-(U$2-PadSD2)") (class "Default")
      (node (ref "U$2") (pin "SD2") (pinfunction "SD2_SD2") (pintype "bidirectional"))
    )
    (net (code "186") (name "unconnected-(U$2-PadSD3)") (class "Default")
      (node (ref "U$2") (pin "SD3") (pinfunction "SD3_SD3") (pintype "bidirectional"))
    )
    (net (code "187") (name "unconnected-(U$2-RSV-PadRSV@0)") (class "Default")
      (node (ref "U$2") (pin "RSV@0") (pinfunction "RSV_RSV@0") (pintype "bidirectional"))
    )
    (net (code "188") (name "unconnected-(U$2-RSV-PadRSV@1)") (class "Default")
      (node (ref "U$2") (pin "RSV@1") (pinfunction "RSV_RSV@1") (pintype "bidirectional"))
    )
    (net (code "189") (name "unconnected-(U$3-Pad5V)") (class "Default")
      (node (ref "U$3") (pin "5V") (pinfunction "5V_5V") (pintype "bidirectional"))
    )
    (net (code "190") (name "unconnected-(U$3-PadB1)") (class "Default")
      (node (ref "U$3") (pin "B1") (pinfunction "B1_B1") (pintype "bidirectional"))
    )
    (net (code "191") (name "unconnected-(U$3-PadB2)") (class "Default")
      (node (ref "U$3") (pin "B2") (pinfunction "B2_B2") (pintype "bidirectional"))
    )
    (net (code "192") (name "unconnected-(U$3-PadB3)") (class "Default")
      (node (ref "U$3") (pin "B3") (pinfunction "B3_B3") (pintype "bidirectional"))
    )
    (net (code "193") (name "unconnected-(U$3-PadB4)") (class "Default")
      (node (ref "U$3") (pin "B4") (pinfunction "B4_B4") (pintype "bidirectional"))
    )
    (net (code "194") (name "unconnected-(U$3-PadB5)") (class "Default")
      (node (ref "U$3") (pin "B5") (pinfunction "B5_B5") (pintype "bidirectional"))
    )
    (net (code "195") (name "unconnected-(U$3-PadB6)") (class "Default")
      (node (ref "U$3") (pin "B6") (pinfunction "B6_B6") (pintype "bidirectional"))
    )
    (net (code "196") (name "unconnected-(U$3-PadB7)") (class "Default")
      (node (ref "U$3") (pin "B7") (pinfunction "B7_B7") (pintype "bidirectional"))
    )
    (net (code "197") (name "unconnected-(U$3-PadD0)") (class "Default")
      (node (ref "U$3") (pin "D0") (pinfunction "D0_D0") (pintype "bidirectional"))
    )
    (net (code "198") (name "unconnected-(U$3-PadD1)") (class "Default")
      (node (ref "U$3") (pin "D1") (pinfunction "D1_D1") (pintype "bidirectional"))
    )
    (net (code "199") (name "unconnected-(U$3-PadSCK)") (class "Default")
      (node (ref "U$3") (pin "SCK") (pinfunction "SCK_SCK") (pintype "bidirectional"))
    )
    (net (code "200") (name "unconnected-(U$3-PadSS)") (class "Default")
      (node (ref "U$3") (pin "SS") (pinfunction "SS_SS") (pintype "bidirectional"))
    )
  )
)
